# ADC_Configuration.net
KiCad netlist of a schematic drawn in Altium Designer
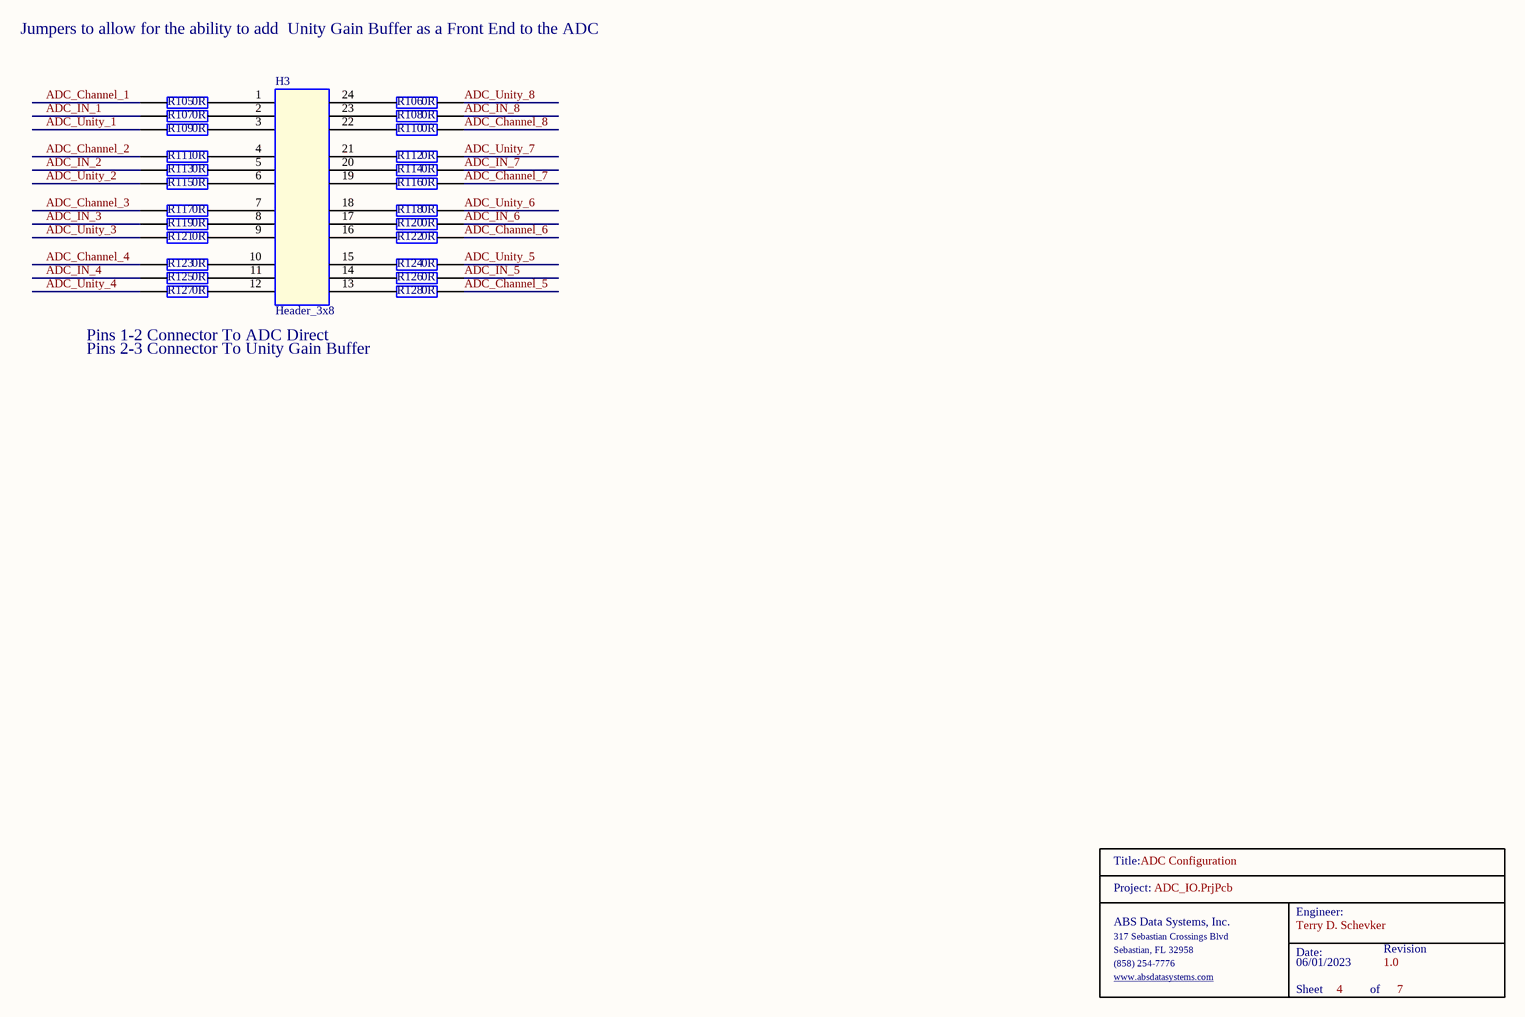
[diagram p0: ADC_Configuration.SchDoc]

(export (version "E")
  (design (tool "Eeschema 10.0.6"))
  (components
    (comp (ref "H3")
      (value "Header_3x8")
      (footprint "HDR3X8")
      (description "16 Pin 3x8 Through Hold Jumprts")
      (fields
        (field (name "MANUFACTURER") "Samtec")
        (field (name "MANUFACTURER PART NUMBER") "TST-108-01-G-D")
      )
      (libsource (lib "Misc") (part "Header_3x8"))
    )
    (comp (ref "R105")
      (value "0R")
      (footprint "0603")
      (description "YAGEO 0603 0 ohm")
      (fields
        (field (name "MOUSER PART NUMBER") "603-RC0603JR-070RL")
        (field (name "MANUFACTURER_PART_NUMBER") "RC0603JR-070RL")
      )
      (libsource (lib "Resistors") (part "RC0603JR-070RL"))
    )
    (comp (ref "R106")
      (value "0R")
      (footprint "0603")
      (description "YAGEO 0603 0 ohm")
      (fields
        (field (name "MOUSER PART NUMBER") "603-RC0603JR-070RL")
        (field (name "MANUFACTURER_PART_NUMBER") "RC0603JR-070RL")
      )
      (libsource (lib "Resistors") (part "RC0603JR-070RL"))
    )
    (comp (ref "R107")
      (value "0R")
      (footprint "0603")
      (description "YAGEO 0603 0 ohm")
      (fields
        (field (name "MOUSER PART NUMBER") "603-RC0603JR-070RL")
        (field (name "MANUFACTURER_PART_NUMBER") "RC0603JR-070RL")
      )
      (libsource (lib "Resistors") (part "RC0603JR-070RL"))
    )
    (comp (ref "R108")
      (value "0R")
      (footprint "0603")
      (description "YAGEO 0603 0 ohm")
      (fields
        (field (name "MOUSER PART NUMBER") "603-RC0603JR-070RL")
        (field (name "MANUFACTURER_PART_NUMBER") "RC0603JR-070RL")
      )
      (libsource (lib "Resistors") (part "RC0603JR-070RL"))
    )
    (comp (ref "R109")
      (value "0R")
      (footprint "0603")
      (description "YAGEO 0603 0 ohm")
      (fields
        (field (name "MOUSER PART NUMBER") "603-RC0603JR-070RL")
        (field (name "MANUFACTURER_PART_NUMBER") "RC0603JR-070RL")
      )
      (libsource (lib "Resistors") (part "RC0603JR-070RL"))
    )
    (comp (ref "R110")
      (value "0R")
      (footprint "0603")
      (description "YAGEO 0603 0 ohm")
      (fields
        (field (name "MOUSER PART NUMBER") "603-RC0603JR-070RL")
        (field (name "MANUFACTURER_PART_NUMBER") "RC0603JR-070RL")
      )
      (libsource (lib "Resistors") (part "RC0603JR-070RL"))
    )
    (comp (ref "R111")
      (value "0R")
      (footprint "0603")
      (description "YAGEO 0603 0 ohm")
      (fields
        (field (name "MOUSER PART NUMBER") "603-RC0603JR-070RL")
        (field (name "MANUFACTURER_PART_NUMBER") "RC0603JR-070RL")
      )
      (libsource (lib "Resistors") (part "RC0603JR-070RL"))
    )
    (comp (ref "R112")
      (value "0R")
      (footprint "0603")
      (description "YAGEO 0603 0 ohm")
      (fields
        (field (name "MOUSER PART NUMBER") "603-RC0603JR-070RL")
        (field (name "MANUFACTURER_PART_NUMBER") "RC0603JR-070RL")
      )
      (libsource (lib "Resistors") (part "RC0603JR-070RL"))
    )
    (comp (ref "R113")
      (value "0R")
      (footprint "0603")
      (description "YAGEO 0603 0 ohm")
      (fields
        (field (name "MOUSER PART NUMBER") "603-RC0603JR-070RL")
        (field (name "MANUFACTURER_PART_NUMBER") "RC0603JR-070RL")
      )
      (libsource (lib "Resistors") (part "RC0603JR-070RL"))
    )
    (comp (ref "R114")
      (value "0R")
      (footprint "0603")
      (description "YAGEO 0603 0 ohm")
      (fields
        (field (name "MOUSER PART NUMBER") "603-RC0603JR-070RL")
        (field (name "MANUFACTURER_PART_NUMBER") "RC0603JR-070RL")
      )
      (libsource (lib "Resistors") (part "RC0603JR-070RL"))
    )
    (comp (ref "R115")
      (value "0R")
      (footprint "0603")
      (description "YAGEO 0603 0 ohm")
      (fields
        (field (name "MOUSER PART NUMBER") "603-RC0603JR-070RL")
        (field (name "MANUFACTURER_PART_NUMBER") "RC0603JR-070RL")
      )
      (libsource (lib "Resistors") (part "RC0603JR-070RL"))
    )
    (comp (ref "R116")
      (value "0R")
      (footprint "0603")
      (description "YAGEO 0603 0 ohm")
      (fields
        (field (name "MOUSER PART NUMBER") "603-RC0603JR-070RL")
        (field (name "MANUFACTURER_PART_NUMBER") "RC0603JR-070RL")
      )
      (libsource (lib "Resistors") (part "RC0603JR-070RL"))
    )
    (comp (ref "R117")
      (value "0R")
      (footprint "0603")
      (description "YAGEO 0603 0 ohm")
      (fields
        (field (name "MOUSER PART NUMBER") "603-RC0603JR-070RL")
        (field (name "MANUFACTURER_PART_NUMBER") "RC0603JR-070RL")
      )
      (libsource (lib "Resistors") (part "RC0603JR-070RL"))
    )
    (comp (ref "R118")
      (value "0R")
      (footprint "0603")
      (description "YAGEO 0603 0 ohm")
      (fields
        (field (name "MOUSER PART NUMBER") "603-RC0603JR-070RL")
        (field (name "MANUFACTURER_PART_NUMBER") "RC0603JR-070RL")
      )
      (libsource (lib "Resistors") (part "RC0603JR-070RL"))
    )
    (comp (ref "R119")
      (value "0R")
      (footprint "0603")
      (description "YAGEO 0603 0 ohm")
      (fields
        (field (name "MOUSER PART NUMBER") "603-RC0603JR-070RL")
        (field (name "MANUFACTURER_PART_NUMBER") "RC0603JR-070RL")
      )
      (libsource (lib "Resistors") (part "RC0603JR-070RL"))
    )
    (comp (ref "R120")
      (value "0R")
      (footprint "0603")
      (description "YAGEO 0603 0 ohm")
      (fields
        (field (name "MOUSER PART NUMBER") "603-RC0603JR-070RL")
        (field (name "MANUFACTURER_PART_NUMBER") "RC0603JR-070RL")
      )
      (libsource (lib "Resistors") (part "RC0603JR-070RL"))
    )
    (comp (ref "R121")
      (value "0R")
      (footprint "0603")
      (description "YAGEO 0603 0 ohm")
      (fields
        (field (name "MOUSER PART NUMBER") "603-RC0603JR-070RL")
        (field (name "MANUFACTURER_PART_NUMBER") "RC0603JR-070RL")
      )
      (libsource (lib "Resistors") (part "RC0603JR-070RL"))
    )
    (comp (ref "R122")
      (value "0R")
      (footprint "0603")
      (description "YAGEO 0603 0 ohm")
      (fields
        (field (name "MOUSER PART NUMBER") "603-RC0603JR-070RL")
        (field (name "MANUFACTURER_PART_NUMBER") "RC0603JR-070RL")
      )
      (libsource (lib "Resistors") (part "RC0603JR-070RL"))
    )
    (comp (ref "R123")
      (value "0R")
      (footprint "0603")
      (description "YAGEO 0603 0 ohm")
      (fields
        (field (name "MOUSER PART NUMBER") "603-RC0603JR-070RL")
        (field (name "MANUFACTURER_PART_NUMBER") "RC0603JR-070RL")
      )
      (libsource (lib "Resistors") (part "RC0603JR-070RL"))
    )
    (comp (ref "R124")
      (value "0R")
      (footprint "0603")
      (description "YAGEO 0603 0 ohm")
      (fields
        (field (name "MOUSER PART NUMBER") "603-RC0603JR-070RL")
        (field (name "MANUFACTURER_PART_NUMBER") "RC0603JR-070RL")
      )
      (libsource (lib "Resistors") (part "RC0603JR-070RL"))
    )
    (comp (ref "R125")
      (value "0R")
      (footprint "0603")
      (description "YAGEO 0603 0 ohm")
      (fields
        (field (name "MOUSER PART NUMBER") "603-RC0603JR-070RL")
        (field (name "MANUFACTURER_PART_NUMBER") "RC0603JR-070RL")
      )
      (libsource (lib "Resistors") (part "RC0603JR-070RL"))
    )
    (comp (ref "R126")
      (value "0R")
      (footprint "0603")
      (description "YAGEO 0603 0 ohm")
      (fields
        (field (name "MOUSER PART NUMBER") "603-RC0603JR-070RL")
        (field (name "MANUFACTURER_PART_NUMBER") "RC0603JR-070RL")
      )
      (libsource (lib "Resistors") (part "RC0603JR-070RL"))
    )
    (comp (ref "R127")
      (value "0R")
      (footprint "0603")
      (description "YAGEO 0603 0 ohm")
      (fields
        (field (name "MOUSER PART NUMBER") "603-RC0603JR-070RL")
        (field (name "MANUFACTURER_PART_NUMBER") "RC0603JR-070RL")
      )
      (libsource (lib "Resistors") (part "RC0603JR-070RL"))
    )
    (comp (ref "R128")
      (value "0R")
      (footprint "0603")
      (description "YAGEO 0603 0 ohm")
      (fields
        (field (name "MOUSER PART NUMBER") "603-RC0603JR-070RL")
        (field (name "MANUFACTURER_PART_NUMBER") "RC0603JR-070RL")
      )
      (libsource (lib "Resistors") (part "RC0603JR-070RL"))
    )
    (comp (ref "TitleBlock_4") (value "TitleBlock") (libsource (lib "Misc") (part "TitleBlock")))
  )
  (nets
    (net (code "1") (name "/ADC_Channel_1") (class "Default")
      (node (ref "R105") (pin "1") (pinfunction "1_1") (pintype "passive"))
    )
    (net (code "2") (name "/ADC_Channel_2") (class "Default")
      (node (ref "R111") (pin "1") (pinfunction "1_1") (pintype "passive"))
    )
    (net (code "3") (name "/ADC_Channel_3") (class "Default")
      (node (ref "R117") (pin "1") (pinfunction "1_1") (pintype "passive"))
    )
    (net (code "4") (name "/ADC_Channel_4") (class "Default")
      (node (ref "R123") (pin "1") (pinfunction "1_1") (pintype "passive"))
    )
    (net (code "5") (name "/ADC_Channel_5") (class "Default")
      (node (ref "R128") (pin "2") (pinfunction "2_2") (pintype "passive"))
    )
    (net (code "6") (name "/ADC_Channel_6") (class "Default")
      (node (ref "R122") (pin "2") (pinfunction "2_2") (pintype "passive"))
    )
    (net (code "7") (name "/ADC_Channel_7") (class "Default")
      (node (ref "R116") (pin "2") (pinfunction "2_2") (pintype "passive"))
    )
    (net (code "8") (name "/ADC_Channel_8") (class "Default")
      (node (ref "R110") (pin "2") (pinfunction "2_2") (pintype "passive"))
    )
    (net (code "9") (name "/ADC_IN_1") (class "Default")
      (node (ref "R107") (pin "1") (pinfunction "1_1") (pintype "passive"))
    )
    (net (code "10") (name "/ADC_IN_2") (class "Default")
      (node (ref "R113") (pin "1") (pinfunction "1_1") (pintype "passive"))
    )
    (net (code "11") (name "/ADC_IN_3") (class "Default")
      (node (ref "R119") (pin "1") (pinfunction "1_1") (pintype "passive"))
    )
    (net (code "12") (name "/ADC_IN_4") (class "Default")
      (node (ref "R125") (pin "1") (pinfunction "1_1") (pintype "passive"))
    )
    (net (code "13") (name "/ADC_IN_5") (class "Default")
      (node (ref "R126") (pin "2") (pinfunction "2_2") (pintype "passive"))
    )
    (net (code "14") (name "/ADC_IN_6") (class "Default")
      (node (ref "R120") (pin "2") (pinfunction "2_2") (pintype "passive"))
    )
    (net (code "15") (name "/ADC_IN_7") (class "Default")
      (node (ref "R114") (pin "2") (pinfunction "2_2") (pintype "passive"))
    )
    (net (code "16") (name "/ADC_IN_8") (class "Default")
      (node (ref "R108") (pin "2") (pinfunction "2_2") (pintype "passive"))
    )
    (net (code "17") (name "/ADC_Unity_1") (class "Default")
      (node (ref "R109") (pin "1") (pinfunction "1_1") (pintype "passive"))
    )
    (net (code "18") (name "/ADC_Unity_2") (class "Default")
      (node (ref "R115") (pin "1") (pinfunction "1_1") (pintype "passive"))
    )
    (net (code "19") (name "/ADC_Unity_3") (class "Default")
      (node (ref "R121") (pin "1") (pinfunction "1_1") (pintype "passive"))
    )
    (net (code "20") (name "/ADC_Unity_4") (class "Default")
      (node (ref "R127") (pin "1") (pinfunction "1_1") (pintype "passive"))
    )
    (net (code "21") (name "/ADC_Unity_5") (class "Default")
      (node (ref "R124") (pin "2") (pinfunction "2_2") (pintype "passive"))
    )
    (net (code "22") (name "/ADC_Unity_6") (class "Default")
      (node (ref "R118") (pin "2") (pinfunction "2_2") (pintype "passive"))
    )
    (net (code "23") (name "/ADC_Unity_7") (class "Default")
      (node (ref "R112") (pin "2") (pinfunction "2_2") (pintype "passive"))
    )
    (net (code "24") (name "/ADC_Unity_8") (class "Default")
      (node (ref "R106") (pin "2") (pinfunction "2_2") (pintype "passive"))
    )
    (net (code "25") (name "Net-(H3-Pad1)") (class "Default")
      (node (ref "H3") (pin "1") (pinfunction "1_1") (pintype "passive"))
      (node (ref "R105") (pin "2") (pinfunction "2_2") (pintype "passive"))
    )
    (net (code "26") (name "Net-(H3-Pad2)") (class "Default")
      (node (ref "H3") (pin "2") (pinfunction "2_2") (pintype "passive"))
      (node (ref "R107") (pin "2") (pinfunction "2_2") (pintype "passive"))
    )
    (net (code "27") (name "Net-(H3-Pad3)") (class "Default")
      (node (ref "H3") (pin "3") (pinfunction "3_3") (pintype "passive"))
      (node (ref "R109") (pin "2") (pinfunction "2_2") (pintype "passive"))
    )
    (net (code "28") (name "Net-(H3-Pad4)") (class "Default")
      (node (ref "H3") (pin "4") (pinfunction "4_4") (pintype "passive"))
      (node (ref "R111") (pin "2") (pinfunction "2_2") (pintype "passive"))
    )
    (net (code "29") (name "Net-(H3-Pad5)") (class "Default")
      (node (ref "H3") (pin "5") (pinfunction "5_5") (pintype "passive"))
      (node (ref "R113") (pin "2") (pinfunction "2_2") (pintype "passive"))
    )
    (net (code "30") (name "Net-(H3-Pad6)") (class "Default")
      (node (ref "H3") (pin "6") (pinfunction "6_6") (pintype "passive"))
      (node (ref "R115") (pin "2") (pinfunction "2_2") (pintype "passive"))
    )
    (net (code "31") (name "Net-(H3-Pad7)") (class "Default")
      (node (ref "H3") (pin "7") (pinfunction "7_7") (pintype "passive"))
      (node (ref "R117") (pin "2") (pinfunction "2_2") (pintype "passive"))
    )
    (net (code "32") (name "Net-(H3-Pad8)") (class "Default")
      (node (ref "H3") (pin "8") (pinfunction "8_8") (pintype "passive"))
      (node (ref "R119") (pin "2") (pinfunction "2_2") (pintype "passive"))
    )
    (net (code "33") (name "Net-(H3-Pad9)") (class "Default")
      (node (ref "H3") (pin "9") (pinfunction "9_9") (pintype "passive"))
      (node (ref "R121") (pin "2") (pinfunction "2_2") (pintype "passive"))
    )
    (net (code "34") (name "Net-(H3-Pad10)") (class "Default")
      (node (ref "H3") (pin "10") (pinfunction "10_10") (pintype "passive"))
      (node (ref "R123") (pin "2") (pinfunction "2_2") (pintype "passive"))
    )
    (net (code "35") (name "Net-(H3-Pad11)") (class "Default")
      (node (ref "H3") (pin "11") (pinfunction "11_11") (pintype "passive"))
      (node (ref "R125") (pin "2") (pinfunction "2_2") (pintype "passive"))
    )
    (net (code "36") (name "Net-(H3-Pad12)") (class "Default")
      (node (ref "H3") (pin "12") (pinfunction "12_12") (pintype "passive"))
      (node (ref "R127") (pin "2") (pinfunction "2_2") (pintype "passive"))
    )
    (net (code "37") (name "Net-(H3-Pad13)") (class "Default")
      (node (ref "H3") (pin "13") (pinfunction "13_13") (pintype "passive"))
      (node (ref "R128") (pin "1") (pinfunction "1_1") (pintype "passive"))
    )
    (net (code "38") (name "Net-(H3-Pad14)") (class "Default")
      (node (ref "H3") (pin "14") (pinfunction "14_14") (pintype "passive"))
      (node (ref "R126") (pin "1") (pinfunction "1_1") (pintype "passive"))
    )
    (net (code "39") (name "Net-(H3-Pad15)") (class "Default")
      (node (ref "H3") (pin "15") (pinfunction "15_15") (pintype "passive"))
      (node (ref "R124") (pin "1") (pinfunction "1_1") (pintype "passive"))
    )
    (net (code "40") (name "Net-(H3-Pad16)") (class "Default")
      (node (ref "H3") (pin "16") (pinfunction "16_16") (pintype "passive"))
      (node (ref "R122") (pin "1") (pinfunction "1_1") (pintype "passive"))
    )
    (net (code "41") (name "Net-(H3-Pad17)") (class "Default")
      (node (ref "H3") (pin "17") (pinfunction "17_17") (pintype "passive"))
      (node (ref "R120") (pin "1") (pinfunction "1_1") (pintype "passive"))
    )
    (net (code "42") (name "Net-(H3-Pad18)") (class "Default")
      (node (ref "H3") (pin "18") (pinfunction "18_18") (pintype "passive"))
      (node (ref "R118") (pin "1") (pinfunction "1_1") (pintype "passive"))
    )
    (net (code "43") (name "Net-(H3-Pad19)") (class "Default")
      (node (ref "H3") (pin "19") (pinfunction "19_19") (pintype "passive"))
      (node (ref "R116") (pin "1") (pinfunction "1_1") (pintype "passive"))
    )
    (net (code "44") (name "Net-(H3-Pad20)") (class "Default")
      (node (ref "H3") (pin "20") (pinfunction "20_20") (pintype "passive"))
      (node (ref "R114") (pin "1") (pinfunction "1_1") (pintype "passive"))
    )
    (net (code "45") (name "Net-(H3-Pad21)") (class "Default")
      (node (ref "H3") (pin "21") (pinfunction "21_21") (pintype "passive"))
      (node (ref "R112") (pin "1") (pinfunction "1_1") (pintype "passive"))
    )
    (net (code "46") (name "Net-(H3-Pad22)") (class "Default")
      (node (ref "H3") (pin "22") (pinfunction "22_22") (pintype "passive"))
      (node (ref "R110") (pin "1") (pinfunction "1_1") (pintype "passive"))
    )
    (net (code "47") (name "Net-(H3-Pad23)") (class "Default")
      (node (ref "H3") (pin "23") (pinfunction "23_23") (pintype "passive"))
      (node (ref "R108") (pin "1") (pinfunction "1_1") (pintype "passive"))
    )
    (net (code "48") (name "Net-(H3-Pad24)") (class "Default")
      (node (ref "H3") (pin "24") (pinfunction "24_24") (pintype "passive"))
      (node (ref "R106") (pin "1") (pinfunction "1_1") (pintype "passive"))
    )
  )
)
